# 10ethernet100.net
KiCad netlist of a schematic drawn in Altium Designer
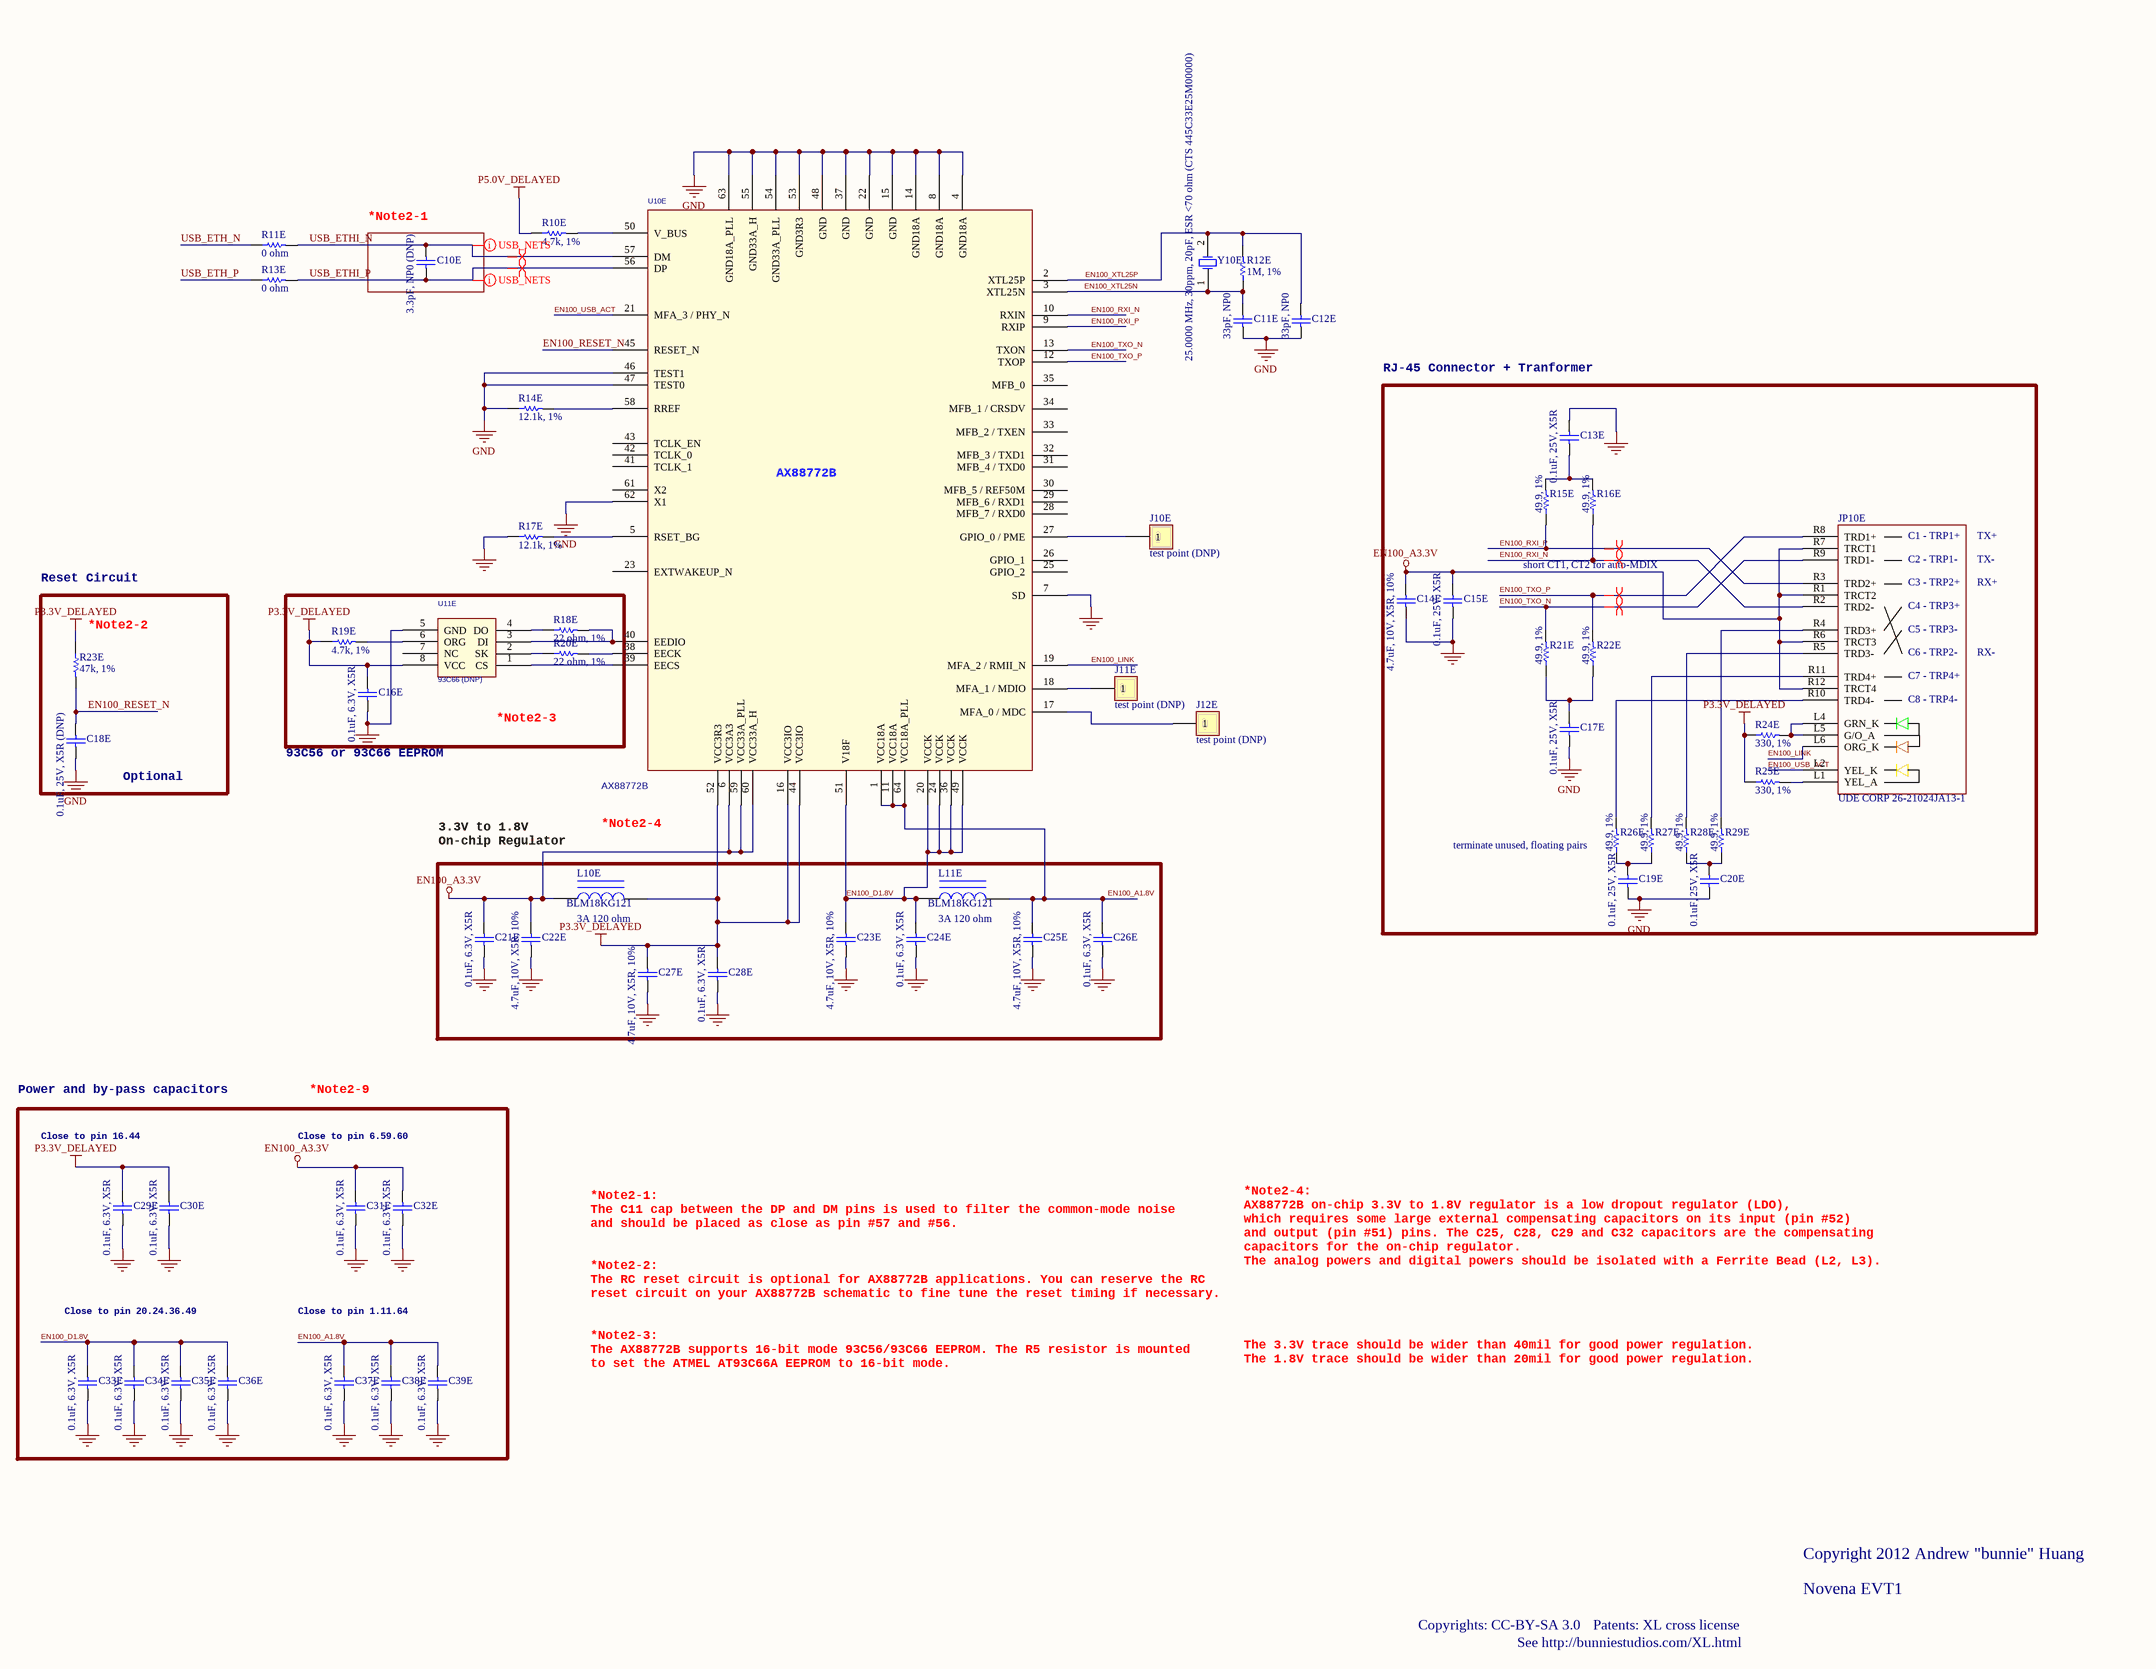
[diagram p0: 10ethernet100.SchDoc]

(export (version "E")
  (design (tool "Eeschema 10.0.6"))
  (components
    (comp (ref "C10E")
      (value "3.3pF, NP0 (DNP)")
      (footprint "CAPC1005N")
      (description "Capacitor (Semiconductor SIM Model)")
      (fields (field (name "PUBLISHER") "Altium Limited"))
      (libsource (lib "Miscellaneous Devices") (part "Cap Semi"))
    )
    (comp (ref "C11E")
      (value "33pF, NP0")
      (footprint "CAPC1005N")
      (description "Capacitor (Semiconductor SIM Model)")
      (fields (field (name "PUBLISHER") "Altium Limited"))
      (libsource (lib "Miscellaneous Devices") (part "Cap Semi"))
    )
    (comp (ref "C12E")
      (value "33pF, NP0")
      (footprint "CAPC1005N")
      (description "Capacitor (Semiconductor SIM Model)")
      (fields (field (name "PUBLISHER") "Altium Limited"))
      (libsource (lib "Miscellaneous Devices") (part "Cap Semi"))
    )
    (comp (ref "C13E")
      (value "0.1uF, 25V, X5R")
      (footprint "CAPC1005N")
      (description "Capacitor (Semiconductor SIM Model)")
      (fields (field (name "PUBLISHER") "Altium Limited"))
      (libsource (lib "Miscellaneous Devices") (part "Cap Semi"))
    )
    (comp (ref "C14E")
      (value "4.7uF, 10V, X5R, 10%")
      (footprint "CAPC1608N")
      (description "Capacitor (Semiconductor SIM Model)")
      (fields (field (name "PUBLISHER") "Altium Limited"))
      (libsource (lib "Miscellaneous Devices") (part "Cap Semi"))
    )
    (comp (ref "C15E")
      (value "0.1uF, 25V, X5R")
      (footprint "CAPC1005N")
      (description "Capacitor (Semiconductor SIM Model)")
      (fields (field (name "PUBLISHER") "Altium Limited"))
      (libsource (lib "Miscellaneous Devices") (part "Cap Semi"))
    )
    (comp (ref "C16E")
      (value "0.1uF, 6.3V, X5R")
      (footprint "CAPC0603N_B")
      (description "Capacitor (Semiconductor SIM Model)")
      (fields (field (name "PUBLISHER") "Altium Limited"))
      (libsource (lib "Miscellaneous Devices") (part "Cap Semi"))
    )
    (comp (ref "C17E")
      (value "0.1uF, 25V, X5R")
      (footprint "CAPC1005N")
      (description "Capacitor (Semiconductor SIM Model)")
      (fields (field (name "PUBLISHER") "Altium Limited"))
      (libsource (lib "Miscellaneous Devices") (part "Cap Semi"))
    )
    (comp (ref "C18E")
      (value "0.1uF, 25V, X5R (DNP)")
      (footprint "CAPC1005N")
      (description "Capacitor (Semiconductor SIM Model)")
      (fields (field (name "PUBLISHER") "Altium Limited"))
      (libsource (lib "Miscellaneous Devices") (part "Cap Semi"))
    )
    (comp (ref "C19E")
      (value "0.1uF, 25V, X5R")
      (footprint "CAPC1005N")
      (description "Capacitor (Semiconductor SIM Model)")
      (fields (field (name "PUBLISHER") "Altium Limited"))
      (libsource (lib "Miscellaneous Devices") (part "Cap Semi"))
    )
    (comp (ref "C20E")
      (value "0.1uF, 25V, X5R")
      (footprint "CAPC1005N")
      (description "Capacitor (Semiconductor SIM Model)")
      (fields (field (name "PUBLISHER") "Altium Limited"))
      (libsource (lib "Miscellaneous Devices") (part "Cap Semi"))
    )
    (comp (ref "C21E")
      (value "0.1uF, 6.3V, X5R")
      (footprint "CAPC0603N_B")
      (description "Capacitor (Semiconductor SIM Model)")
      (fields (field (name "PUBLISHER") "Altium Limited"))
      (libsource (lib "Miscellaneous Devices") (part "Cap Semi"))
    )
    (comp (ref "C22E")
      (value "4.7uF, 10V, X5R, 10%")
      (footprint "CAPC1608N")
      (description "Capacitor (Semiconductor SIM Model)")
      (fields (field (name "PUBLISHER") "Altium Limited"))
      (libsource (lib "Miscellaneous Devices") (part "Cap Semi"))
    )
    (comp (ref "C23E")
      (value "4.7uF, 10V, X5R, 10%")
      (footprint "CAPC1608N")
      (description "Capacitor (Semiconductor SIM Model)")
      (fields (field (name "PUBLISHER") "Altium Limited"))
      (libsource (lib "Miscellaneous Devices") (part "Cap Semi"))
    )
    (comp (ref "C24E")
      (value "0.1uF, 6.3V, X5R")
      (footprint "CAPC0603N_B")
      (description "Capacitor (Semiconductor SIM Model)")
      (fields (field (name "PUBLISHER") "Altium Limited"))
      (libsource (lib "Miscellaneous Devices") (part "Cap Semi"))
    )
    (comp (ref "C25E")
      (value "4.7uF, 10V, X5R, 10%")
      (footprint "CAPC1608N")
      (description "Capacitor (Semiconductor SIM Model)")
      (fields (field (name "PUBLISHER") "Altium Limited"))
      (libsource (lib "Miscellaneous Devices") (part "Cap Semi"))
    )
    (comp (ref "C26E")
      (value "0.1uF, 6.3V, X5R")
      (footprint "CAPC0603N_B")
      (description "Capacitor (Semiconductor SIM Model)")
      (fields (field (name "PUBLISHER") "Altium Limited"))
      (libsource (lib "Miscellaneous Devices") (part "Cap Semi"))
    )
    (comp (ref "C27E")
      (value "4.7uF, 10V, X5R, 10%")
      (footprint "CAPC1608N")
      (description "Capacitor (Semiconductor SIM Model)")
      (fields (field (name "PUBLISHER") "Altium Limited"))
      (libsource (lib "Miscellaneous Devices") (part "Cap Semi"))
    )
    (comp (ref "C28E")
      (value "0.1uF, 6.3V, X5R")
      (footprint "CAPC0603N_B")
      (description "Capacitor (Semiconductor SIM Model)")
      (fields (field (name "PUBLISHER") "Altium Limited"))
      (libsource (lib "Miscellaneous Devices") (part "Cap Semi"))
    )
    (comp (ref "C29E")
      (value "0.1uF, 6.3V, X5R")
      (footprint "CAPC0603N_B")
      (description "Capacitor (Semiconductor SIM Model)")
      (fields (field (name "PUBLISHER") "Altium Limited"))
      (libsource (lib "Miscellaneous Devices") (part "Cap Semi"))
    )
    (comp (ref "C30E")
      (value "0.1uF, 6.3V, X5R")
      (footprint "CAPC0603N_B")
      (description "Capacitor (Semiconductor SIM Model)")
      (fields (field (name "PUBLISHER") "Altium Limited"))
      (libsource (lib "Miscellaneous Devices") (part "Cap Semi"))
    )
    (comp (ref "C31E")
      (value "0.1uF, 6.3V, X5R")
      (footprint "CAPC0603N_B")
      (description "Capacitor (Semiconductor SIM Model)")
      (fields (field (name "PUBLISHER") "Altium Limited"))
      (libsource (lib "Miscellaneous Devices") (part "Cap Semi"))
    )
    (comp (ref "C32E")
      (value "0.1uF, 6.3V, X5R")
      (footprint "CAPC0603N_B")
      (description "Capacitor (Semiconductor SIM Model)")
      (fields (field (name "PUBLISHER") "Altium Limited"))
      (libsource (lib "Miscellaneous Devices") (part "Cap Semi"))
    )
    (comp (ref "C33E")
      (value "0.1uF, 6.3V, X5R")
      (footprint "CAPC0603N_B")
      (description "Capacitor (Semiconductor SIM Model)")
      (fields (field (name "PUBLISHER") "Altium Limited"))
      (libsource (lib "Miscellaneous Devices") (part "Cap Semi"))
    )
    (comp (ref "C34E")
      (value "0.1uF, 6.3V, X5R")
      (footprint "CAPC0603N_B")
      (description "Capacitor (Semiconductor SIM Model)")
      (fields (field (name "PUBLISHER") "Altium Limited"))
      (libsource (lib "Miscellaneous Devices") (part "Cap Semi"))
    )
    (comp (ref "C35E")
      (value "0.1uF, 6.3V, X5R")
      (footprint "CAPC0603N_B")
      (description "Capacitor (Semiconductor SIM Model)")
      (fields (field (name "PUBLISHER") "Altium Limited"))
      (libsource (lib "Miscellaneous Devices") (part "Cap Semi"))
    )
    (comp (ref "C36E")
      (value "0.1uF, 6.3V, X5R")
      (footprint "CAPC0603N_B")
      (description "Capacitor (Semiconductor SIM Model)")
      (fields (field (name "PUBLISHER") "Altium Limited"))
      (libsource (lib "Miscellaneous Devices") (part "Cap Semi"))
    )
    (comp (ref "C37E")
      (value "0.1uF, 6.3V, X5R")
      (footprint "CAPC0603N_B")
      (description "Capacitor (Semiconductor SIM Model)")
      (fields (field (name "PUBLISHER") "Altium Limited"))
      (libsource (lib "Miscellaneous Devices") (part "Cap Semi"))
    )
    (comp (ref "C38E")
      (value "0.1uF, 6.3V, X5R")
      (footprint "CAPC0603N_B")
      (description "Capacitor (Semiconductor SIM Model)")
      (fields (field (name "PUBLISHER") "Altium Limited"))
      (libsource (lib "Miscellaneous Devices") (part "Cap Semi"))
    )
    (comp (ref "C39E")
      (value "0.1uF, 6.3V, X5R")
      (footprint "CAPC0603N_B")
      (description "Capacitor (Semiconductor SIM Model)")
      (fields (field (name "PUBLISHER") "Altium Limited"))
      (libsource (lib "Miscellaneous Devices") (part "Cap Semi"))
    )
    (comp (ref "J10E")
      (value "test point (DNP)")
      (footprint "TP_SMT_38mil")
      (description "Connector")
      (libsource (lib "*") (part "CON1"))
    )
    (comp (ref "J11E")
      (value "test point (DNP)")
      (footprint "TP_SMT_38mil")
      (description "Connector")
      (libsource (lib "*") (part "CON1"))
    )
    (comp (ref "J12E")
      (value "test point (DNP)")
      (footprint "TP_SMT_38mil")
      (description "Connector")
      (libsource (lib "*") (part "CON1"))
    )
    (comp (ref "JP10E")
      (value "UDE CORP 26-21024JA13-1")
      (footprint "UDE_CORP_26-21024JA13-1")
      (description "10/100/1000BT + magnetics, symmetric, tab up, with LEDs")
      (libsource (lib "commonsch") (part "UDE_CORP_26-21024JA13-1"))
    )
    (comp (ref "L10E")
      (value "BLM18KG121")
      (footprint "INDC1608AN")
      (description "Magnetic-Core Inductor")
      (fields (field (name "ALTIUM_VALUE") "3A 120 ohm") (field (name "PUBLISHER") "Altium Limited"))
      (libsource (lib "Miscellaneous Devices") (part "Inductor Iron"))
    )
    (comp (ref "L11E")
      (value "BLM18KG121")
      (footprint "INDC1608AN")
      (description "Magnetic-Core Inductor")
      (fields (field (name "ALTIUM_VALUE") "3A 120 ohm") (field (name "PUBLISHER") "Altium Limited"))
      (libsource (lib "Miscellaneous Devices") (part "Inductor Iron"))
    )
    (comp (ref "R10E")
      (value "4.7k, 1%")
      (footprint "RESC1005N")
      (description "Resistor")
      (fields (field (name "PUBLISHER") "Altium Limited"))
      (libsource (lib "Miscellaneous Devices") (part "Res1"))
    )
    (comp (ref "R11E")
      (value "0 ohm")
      (footprint "RESC1005N")
      (description "Resistor")
      (fields (field (name "PUBLISHER") "Altium Limited"))
      (libsource (lib "Miscellaneous Devices") (part "Res1"))
    )
    (comp (ref "R12E")
      (value "1M, 1%")
      (footprint "RESC1005N")
      (description "Resistor")
      (fields (field (name "PUBLISHER") "Altium Limited"))
      (libsource (lib "Miscellaneous Devices") (part "Res1"))
    )
    (comp (ref "R13E")
      (value "0 ohm")
      (footprint "RESC1005N")
      (description "Resistor")
      (fields (field (name "PUBLISHER") "Altium Limited"))
      (libsource (lib "Miscellaneous Devices") (part "Res1"))
    )
    (comp (ref "R14E")
      (value "12.1k, 1%")
      (footprint "RESC1005N")
      (description "Resistor")
      (fields (field (name "PUBLISHER") "Altium Limited"))
      (libsource (lib "Miscellaneous Devices") (part "Res1"))
    )
    (comp (ref "R15E")
      (value "49.9, 1%")
      (footprint "RESC1005N")
      (description "Resistor")
      (fields (field (name "PUBLISHER") "Altium Limited"))
      (libsource (lib "Miscellaneous Devices") (part "Res1"))
    )
    (comp (ref "R16E")
      (value "49.9, 1%")
      (footprint "RESC1005N")
      (description "Resistor")
      (fields (field (name "PUBLISHER") "Altium Limited"))
      (libsource (lib "Miscellaneous Devices") (part "Res1"))
    )
    (comp (ref "R17E")
      (value "12.1k, 1%")
      (footprint "RESC1005N")
      (description "Resistor")
      (fields (field (name "PUBLISHER") "Altium Limited"))
      (libsource (lib "Miscellaneous Devices") (part "Res1"))
    )
    (comp (ref "R18E")
      (value "22 ohm, 1%")
      (footprint "RESC1005N")
      (description "Resistor")
      (fields (field (name "PUBLISHER") "Altium Limited"))
      (libsource (lib "Miscellaneous Devices") (part "Res1"))
    )
    (comp (ref "R19E")
      (value "4.7k, 1%")
      (footprint "RESC1005N")
      (description "Resistor")
      (fields (field (name "PUBLISHER") "Altium Limited"))
      (libsource (lib "Miscellaneous Devices") (part "Res1"))
    )
    (comp (ref "R20E")
      (value "22 ohm, 1%")
      (footprint "RESC1005N")
      (description "Resistor")
      (fields (field (name "PUBLISHER") "Altium Limited"))
      (libsource (lib "Miscellaneous Devices") (part "Res1"))
    )
    (comp (ref "R21E")
      (value "49.9, 1%")
      (footprint "RESC1005N")
      (description "Resistor")
      (fields (field (name "PUBLISHER") "Altium Limited"))
      (libsource (lib "Miscellaneous Devices") (part "Res1"))
    )
    (comp (ref "R22E")
      (value "49.9, 1%")
      (footprint "RESC1005N")
      (description "Resistor")
      (fields (field (name "PUBLISHER") "Altium Limited"))
      (libsource (lib "Miscellaneous Devices") (part "Res1"))
    )
    (comp (ref "R23E")
      (value "47k, 1%")
      (footprint "RESC1005N")
      (description "Resistor")
      (fields (field (name "PUBLISHER") "Altium Limited"))
      (libsource (lib "Miscellaneous Devices") (part "Res1"))
    )
    (comp (ref "R24E")
      (value "330, 1%")
      (footprint "RESC1005N")
      (description "Resistor")
      (fields (field (name "PUBLISHER") "Altium Limited"))
      (libsource (lib "Miscellaneous Devices") (part "Res1"))
    )
    (comp (ref "R25E")
      (value "330, 1%")
      (footprint "RESC1005N")
      (description "Resistor")
      (fields (field (name "PUBLISHER") "Altium Limited"))
      (libsource (lib "Miscellaneous Devices") (part "Res1"))
    )
    (comp (ref "R26E")
      (value "49.9, 1%")
      (footprint "RESC1005N")
      (description "Resistor")
      (fields (field (name "PUBLISHER") "Altium Limited"))
      (libsource (lib "Miscellaneous Devices") (part "Res1"))
    )
    (comp (ref "R27E")
      (value "49.9, 1%")
      (footprint "RESC1005N")
      (description "Resistor")
      (fields (field (name "PUBLISHER") "Altium Limited"))
      (libsource (lib "Miscellaneous Devices") (part "Res1"))
    )
    (comp (ref "R28E")
      (value "49.9, 1%")
      (footprint "RESC1005N")
      (description "Resistor")
      (fields (field (name "PUBLISHER") "Altium Limited"))
      (libsource (lib "Miscellaneous Devices") (part "Res1"))
    )
    (comp (ref "R29E")
      (value "49.9, 1%")
      (footprint "RESC1005N")
      (description "Resistor")
      (fields (field (name "PUBLISHER") "Altium Limited"))
      (libsource (lib "Miscellaneous Devices") (part "Res1"))
    )
    (comp (ref "U10E") (value "AX88772B") (libsource (lib "*") (part "AX88772B_28")))
    (comp (ref "U11E") (value "93C66 (DNP)") (libsource (lib "*") (part "93c66_0")))
    (comp (ref "Y10E")
      (value "25.0000 MHz, 30ppm, 20pF, ESR <70 ohm (CTS 445C33E25M00000)")
      (footprint "NDK_NX5032A")
      (description "Crystal Oscillator")
      (fields (field (name "PUBLISHER") "Altium Limited"))
      (libsource (lib "Miscellaneous Devices") (part "XTAL"))
    )
  )
  (nets
    (net (code "1") (name "/EN100_A1.8V") (class "Default")
      (node (ref "C25E") (pin "1") (pinfunction "1_1") (pintype "passive"))
      (node (ref "C26E") (pin "1") (pinfunction "1_1") (pintype "passive"))
      (node (ref "C37E") (pin "1") (pinfunction "1_1") (pintype "passive"))
      (node (ref "C38E") (pin "1") (pinfunction "1_1") (pintype "passive"))
      (node (ref "C39E") (pin "1") (pinfunction "1_1") (pintype "passive"))
      (node (ref "L11E") (pin "2") (pinfunction "2_2") (pintype "passive"))
      (node (ref "U10E") (pin "1") (pinfunction "VCC18A_1") (pintype "passive"))
      (node (ref "U10E") (pin "11") (pinfunction "VCC18A_11") (pintype "passive"))
      (node (ref "U10E") (pin "64") (pinfunction "VCC18A_PLL_64") (pintype "passive"))
    )
    (net (code "2") (name "/EN100_D1.8V") (class "Default")
      (node (ref "C23E") (pin "1") (pinfunction "1_1") (pintype "passive"))
      (node (ref "C24E") (pin "1") (pinfunction "1_1") (pintype "passive"))
      (node (ref "C33E") (pin "1") (pinfunction "1_1") (pintype "passive"))
      (node (ref "C34E") (pin "1") (pinfunction "1_1") (pintype "passive"))
      (node (ref "C35E") (pin "1") (pinfunction "1_1") (pintype "passive"))
      (node (ref "C36E") (pin "1") (pinfunction "1_1") (pintype "passive"))
      (node (ref "L11E") (pin "1") (pinfunction "1_1") (pintype "passive"))
      (node (ref "U10E") (pin "20") (pinfunction "VCCK_20") (pintype "passive"))
      (node (ref "U10E") (pin "24") (pinfunction "VCCK_24") (pintype "passive"))
      (node (ref "U10E") (pin "36") (pinfunction "VCCK_36") (pintype "passive"))
      (node (ref "U10E") (pin "49") (pinfunction "VCCK_49") (pintype "passive"))
      (node (ref "U10E") (pin "51") (pinfunction "V18F_51") (pintype "passive"))
    )
    (net (code "3") (name "/EN100_LINK") (class "Default")
      (node (ref "JP10E") (pin "L6") (pinfunction "ORG_K_L6") (pintype "passive"))
      (node (ref "U10E") (pin "19") (pinfunction "MFA_2_/_RMII_N_19") (pintype "passive"))
    )
    (net (code "4") (name "/EN100_RESET_N") (class "Default")
      (node (ref "C18E") (pin "1") (pinfunction "1_1") (pintype "passive"))
      (node (ref "R23E") (pin "2") (pinfunction "2_2") (pintype "passive"))
      (node (ref "U10E") (pin "45") (pinfunction "RESET_N_45") (pintype "passive"))
    )
    (net (code "5") (name "/EN100_RXI_N") (class "Default")
      (node (ref "JP10E") (pin "R2") (pinfunction "TRD2-_R2") (pintype "passive"))
      (node (ref "R16E") (pin "1") (pinfunction "1_1") (pintype "passive"))
      (node (ref "U10E") (pin "10") (pinfunction "RXIN_10") (pintype "passive"))
    )
    (net (code "6") (name "/EN100_RXI_P") (class "Default")
      (node (ref "JP10E") (pin "R3") (pinfunction "TRD2+_R3") (pintype "passive"))
      (node (ref "R15E") (pin "1") (pinfunction "1_1") (pintype "passive"))
      (node (ref "U10E") (pin "9") (pinfunction "RXIP_9") (pintype "passive"))
    )
    (net (code "7") (name "/EN100_TXO_N") (class "Default")
      (node (ref "JP10E") (pin "R9") (pinfunction "TRD1-_R9") (pintype "passive"))
      (node (ref "R21E") (pin "2") (pinfunction "2_2") (pintype "passive"))
      (node (ref "U10E") (pin "13") (pinfunction "TXON_13") (pintype "passive"))
    )
    (net (code "8") (name "/EN100_TXO_P") (class "Default")
      (node (ref "JP10E") (pin "R8") (pinfunction "TRD1+_R8") (pintype "passive"))
      (node (ref "R22E") (pin "2") (pinfunction "2_2") (pintype "passive"))
      (node (ref "U10E") (pin "12") (pinfunction "TXOP_12") (pintype "passive"))
    )
    (net (code "9") (name "/EN100_USB_ACT") (class "Default")
      (node (ref "JP10E") (pin "L2") (pinfunction "YEL_K_L2") (pintype "passive"))
      (node (ref "U10E") (pin "21") (pinfunction "MFA_3_/_PHY_N_21") (pintype "passive"))
    )
    (net (code "10") (name "/EN100_XTL25N") (class "Default")
      (node (ref "C11E") (pin "1") (pinfunction "1_1") (pintype "passive"))
      (node (ref "R12E") (pin "1") (pinfunction "1_1") (pintype "passive"))
      (node (ref "U10E") (pin "3") (pinfunction "XTL25N_3") (pintype "passive"))
      (node (ref "Y10E") (pin "1") (pinfunction "OSC1_1") (pintype "passive"))
    )
    (net (code "11") (name "/EN100_XTL25P") (class "Default")
      (node (ref "C12E") (pin "1") (pinfunction "1_1") (pintype "passive"))
      (node (ref "R12E") (pin "2") (pinfunction "2_2") (pintype "passive"))
      (node (ref "U10E") (pin "2") (pinfunction "XTL25P_2") (pintype "passive"))
      (node (ref "Y10E") (pin "2") (pinfunction "OSC2_2") (pintype "passive"))
    )
    (net (code "12") (name "/USB_ETHI_N") (class "Default")
      (node (ref "C10E") (pin "1") (pinfunction "1_1") (pintype "passive"))
      (node (ref "R11E") (pin "2") (pinfunction "2_2") (pintype "passive"))
      (node (ref "U10E") (pin "57") (pinfunction "DM_57") (pintype "passive"))
    )
    (net (code "13") (name "/USB_ETHI_P") (class "Default")
      (node (ref "C10E") (pin "2") (pinfunction "2_2") (pintype "passive"))
      (node (ref "R13E") (pin "2") (pinfunction "2_2") (pintype "passive"))
      (node (ref "U10E") (pin "56") (pinfunction "DP_56") (pintype "passive"))
    )
    (net (code "14") (name "/USB_ETH_N") (class "Default")
      (node (ref "R11E") (pin "1") (pinfunction "1_1") (pintype "passive"))
    )
    (net (code "15") (name "/USB_ETH_P") (class "Default")
      (node (ref "R13E") (pin "1") (pinfunction "1_1") (pintype "passive"))
    )
    (net (code "16") (name "EN100_A3.3V") (class "Default")
      (node (ref "C14E") (pin "1") (pinfunction "1_1") (pintype "passive"))
      (node (ref "C15E") (pin "1") (pinfunction "1_1") (pintype "passive"))
      (node (ref "C21E") (pin "1") (pinfunction "1_1") (pintype "passive"))
      (node (ref "C22E") (pin "1") (pinfunction "1_1") (pintype "passive"))
      (node (ref "C31E") (pin "1") (pinfunction "1_1") (pintype "passive"))
      (node (ref "C32E") (pin "1") (pinfunction "1_1") (pintype "passive"))
      (node (ref "JP10E") (pin "R1") (pinfunction "TRCT2_R1") (pintype "passive"))
      (node (ref "JP10E") (pin "R12") (pinfunction "TRCT4_R12") (pintype "passive"))
      (node (ref "JP10E") (pin "R6") (pinfunction "TRCT3_R6") (pintype "passive"))
      (node (ref "JP10E") (pin "R7") (pinfunction "TRCT1_R7") (pintype "passive"))
      (node (ref "L10E") (pin "1") (pinfunction "1_1") (pintype "passive"))
      (node (ref "U10E") (pin "59") (pinfunction "VCC33A_PLL_59") (pintype "passive"))
      (node (ref "U10E") (pin "6") (pinfunction "VCC3A3_6") (pintype "passive"))
      (node (ref "U10E") (pin "60") (pinfunction "VCC33A_H_60") (pintype "passive"))
    )
    (net (code "17") (name "GND") (class "Default")
      (node (ref "C11E") (pin "2") (pinfunction "2_2") (pintype "passive"))
      (node (ref "C12E") (pin "2") (pinfunction "2_2") (pintype "passive"))
      (node (ref "C13E") (pin "1") (pinfunction "1_1") (pintype "passive"))
      (node (ref "C14E") (pin "2") (pinfunction "2_2") (pintype "passive"))
      (node (ref "C15E") (pin "2") (pinfunction "2_2") (pintype "passive"))
      (node (ref "C16E") (pin "2") (pinfunction "2_2") (pintype "passive"))
      (node (ref "C17E") (pin "2") (pinfunction "2_2") (pintype "passive"))
      (node (ref "C18E") (pin "2") (pinfunction "2_2") (pintype "passive"))
      (node (ref "C19E") (pin "2") (pinfunction "2_2") (pintype "passive"))
      (node (ref "C20E") (pin "2") (pinfunction "2_2") (pintype "passive"))
      (node (ref "C21E") (pin "2") (pinfunction "2_2") (pintype "passive"))
      (node (ref "C22E") (pin "2") (pinfunction "2_2") (pintype "passive"))
      (node (ref "C23E") (pin "2") (pinfunction "2_2") (pintype "passive"))
      (node (ref "C24E") (pin "2") (pinfunction "2_2") (pintype "passive"))
      (node (ref "C25E") (pin "2") (pinfunction "2_2") (pintype "passive"))
      (node (ref "C26E") (pin "2") (pinfunction "2_2") (pintype "passive"))
      (node (ref "C27E") (pin "2") (pinfunction "2_2") (pintype "passive"))
      (node (ref "C28E") (pin "2") (pinfunction "2_2") (pintype "passive"))
      (node (ref "C29E") (pin "2") (pinfunction "2_2") (pintype "passive"))
      (node (ref "C30E") (pin "2") (pinfunction "2_2") (pintype "passive"))
      (node (ref "C31E") (pin "2") (pinfunction "2_2") (pintype "passive"))
      (node (ref "C32E") (pin "2") (pinfunction "2_2") (pintype "passive"))
      (node (ref "C33E") (pin "2") (pinfunction "2_2") (pintype "passive"))
      (node (ref "C34E") (pin "2") (pinfunction "2_2") (pintype "passive"))
      (node (ref "C35E") (pin "2") (pinfunction "2_2") (pintype "passive"))
      (node (ref "C36E") (pin "2") (pinfunction "2_2") (pintype "passive"))
      (node (ref "C37E") (pin "2") (pinfunction "2_2") (pintype "passive"))
      (node (ref "C38E") (pin "2") (pinfunction "2_2") (pintype "passive"))
      (node (ref "C39E") (pin "2") (pinfunction "2_2") (pintype "passive"))
      (node (ref "R14E") (pin "1") (pinfunction "1_1") (pintype "passive"))
      (node (ref "R17E") (pin "1") (pinfunction "1_1") (pintype "passive"))
      (node (ref "U10E") (pin "14") (pinfunction "GND18A_14") (pintype "passive"))
      (node (ref "U10E") (pin "15") (pinfunction "GND_15") (pintype "passive"))
      (node (ref "U10E") (pin "22") (pinfunction "GND_22") (pintype "passive"))
      (node (ref "U10E") (pin "37") (pinfunction "GND_37") (pintype "passive"))
      (node (ref "U10E") (pin "4") (pinfunction "GND18A_4") (pintype "passive"))
      (node (ref "U10E") (pin "46") (pinfunction "TEST1_46") (pintype "passive"))
      (node (ref "U10E") (pin "47") (pinfunction "TEST0_47") (pintype "passive"))
      (node (ref "U10E") (pin "48") (pinfunction "GND_48") (pintype "passive"))
      (node (ref "U10E") (pin "53") (pinfunction "GND3R3_53") (pintype "passive"))
      (node (ref "U10E") (pin "54") (pinfunction "GND33A_PLL_54") (pintype "passive"))
      (node (ref "U10E") (pin "55") (pinfunction "GND33A_H_55") (pintype "passive"))
      (node (ref "U10E") (pin "62") (pinfunction "X1_62") (pintype "passive"))
      (node (ref "U10E") (pin "63") (pinfunction "GND18A_PLL_63") (pintype "passive"))
      (node (ref "U10E") (pin "7") (pinfunction "SD_7") (pintype "passive"))
      (node (ref "U10E") (pin "8") (pinfunction "GND18A_8") (pintype "passive"))
      (node (ref "U11E") (pin "5") (pinfunction "GND_5") (pintype "passive"))
    )
    (net (code "18") (name "Net-(C13E-Pad2)") (class "Default")
      (node (ref "C13E") (pin "2") (pinfunction "2_2") (pintype "passive"))
      (node (ref "R15E") (pin "2") (pinfunction "2_2") (pintype "passive"))
      (node (ref "R16E") (pin "2") (pinfunction "2_2") (pintype "passive"))
    )
    (net (code "19") (name "Net-(C17E-Pad1)") (class "Default")
      (node (ref "C17E") (pin "1") (pinfunction "1_1") (pintype "passive"))
      (node (ref "R21E") (pin "1") (pinfunction "1_1") (pintype "passive"))
      (node (ref "R22E") (pin "1") (pinfunction "1_1") (pintype "passive"))
    )
    (net (code "20") (name "Net-(C19E-Pad1)") (class "Default")
      (node (ref "C19E") (pin "1") (pinfunction "1_1") (pintype "passive"))
      (node (ref "R26E") (pin "1") (pinfunction "1_1") (pintype "passive"))
      (node (ref "R27E") (pin "1") (pinfunction "1_1") (pintype "passive"))
    )
    (net (code "21") (name "Net-(C20E-Pad1)") (class "Default")
      (node (ref "C20E") (pin "1") (pinfunction "1_1") (pintype "passive"))
      (node (ref "R28E") (pin "1") (pinfunction "1_1") (pintype "passive"))
      (node (ref "R29E") (pin "1") (pinfunction "1_1") (pintype "passive"))
    )
    (net (code "22") (name "Net-(JP10E-GRN_K)") (class "Default")
      (node (ref "JP10E") (pin "L4") (pinfunction "GRN_K_L4") (pintype "passive"))
      (node (ref "JP10E") (pin "L5") (pinfunction "G/O_A_L5") (pintype "passive"))
      (node (ref "R24E") (pin "2") (pinfunction "2_2") (pintype "passive"))
    )
    (net (code "23") (name "Net-(JP10E-TRD3+)") (class "Default")
      (node (ref "JP10E") (pin "R4") (pinfunction "TRD3+_R4") (pintype "passive"))
      (node (ref "R29E") (pin "2") (pinfunction "2_2") (pintype "passive"))
    )
    (net (code "24") (name "Net-(JP10E-TRD3-)") (class "Default")
      (node (ref "JP10E") (pin "R5") (pinfunction "TRD3-_R5") (pintype "passive"))
      (node (ref "R28E") (pin "2") (pinfunction "2_2") (pintype "passive"))
    )
    (net (code "25") (name "Net-(JP10E-TRD4+)") (class "Default")
      (node (ref "JP10E") (pin "R11") (pinfunction "TRD4+_R11") (pintype "passive"))
      (node (ref "R27E") (pin "2") (pinfunction "2_2") (pintype "passive"))
    )
    (net (code "26") (name "Net-(JP10E-TRD4-)") (class "Default")
      (node (ref "JP10E") (pin "R10") (pinfunction "TRD4-_R10") (pintype "passive"))
      (node (ref "R26E") (pin "2") (pinfunction "2_2") (pintype "passive"))
    )
    (net (code "27") (name "Net-(JP10E-YEL_A)") (class "Default")
      (node (ref "JP10E") (pin "L1") (pinfunction "YEL_A_L1") (pintype "passive"))
      (node (ref "R25E") (pin "2") (pinfunction "2_2") (pintype "passive"))
    )
    (net (code "28") (name "Net-(U10E-EECK)") (class "Default")
      (node (ref "R20E") (pin "2") (pinfunction "2_2") (pintype "passive"))
      (node (ref "U10E") (pin "38") (pinfunction "EECK_38") (pintype "passive"))
    )
    (net (code "29") (name "Net-(U10E-EECS)") (class "Default")
      (node (ref "U10E") (pin "39") (pinfunction "EECS_39") (pintype "passive"))
      (node (ref "U11E") (pin "1") (pinfunction "CS_1") (pintype "passive"))
    )
    (net (code "30") (name "Net-(U10E-EEDIO)") (class "Default")
      (node (ref "R18E") (pin "2") (pinfunction "2_2") (pintype "passive"))
      (node (ref "U10E") (pin "40") (pinfunction "EEDIO_40") (pintype "passive"))
      (node (ref "U11E") (pin "3") (pinfunction "DI_3") (pintype "passive"))
    )
    (net (code "31") (name "Net-(U10E-GPIO_0_{slash}_PME)") (class "Default")
      (node (ref "J10E") (pin "1") (pinfunction "1_1") (pintype "passive"))
      (node (ref "U10E") (pin "27") (pinfunction "GPIO_0_/_PME_27") (pintype "passive"))
    )
    (net (code "32") (name "Net-(U10E-MFA_0_{slash}_MDC)") (class "Default")
      (node (ref "J12E") (pin "1") (pinfunction "1_1") (pintype "passive"))
      (node (ref "U10E") (pin "17") (pinfunction "MFA_0_/_MDC_17") (pintype "passive"))
    )
    (net (code "33") (name "Net-(U10E-MFA_1_{slash}_MDIO)") (class "Default")
      (node (ref "J11E") (pin "1") (pinfunction "1_1") (pintype "passive"))
      (node (ref "U10E") (pin "18") (pinfunction "MFA_1_/_MDIO_18") (pintype "passive"))
    )
    (net (code "34") (name "Net-(U10E-RREF)") (class "Default")
      (node (ref "R14E") (pin "2") (pinfunction "2_2") (pintype "passive"))
      (node (ref "U10E") (pin "58") (pinfunction "RREF_58") (pintype "passive"))
    )
    (net (code "35") (name "Net-(U10E-RSET_BG)") (class "Default")
      (node (ref "R17E") (pin "2") (pinfunction "2_2") (pintype "passive"))
      (node (ref "U10E") (pin "5") (pinfunction "RSET_BG_5") (pintype "passive"))
    )
    (net (code "36") (name "Net-(U10E-V_BUS)") (class "Default")
      (node (ref "R10E") (pin "2") (pinfunction "2_2") (pintype "passive"))
      (node (ref "U10E") (pin "50") (pinfunction "V_BUS_50") (pintype "passive"))
    )
    (net (code "37") (name "Net-(U11E-DO)") (class "Default")
      (node (ref "R18E") (pin "1") (pinfunction "1_1") (pintype "passive"))
      (node (ref "U11E") (pin "4") (pinfunction "DO_4") (pintype "passive"))
    )
    (net (code "38") (name "Net-(U11E-ORG)") (class "Default")
      (node (ref "R19E") (pin "2") (pinfunction "2_2") (pintype "passive"))
      (node (ref "U11E") (pin "6") (pinfunction "ORG_6") (pintype "passive"))
    )
    (net (code "39") (name "Net-(U11E-SK)") (class "Default")
      (node (ref "R20E") (pin "1") (pinfunction "1_1") (pintype "passive"))
      (node (ref "U11E") (pin "2") (pinfunction "SK_2") (pintype "passive"))
    )
    (net (code "40") (name "P3.3V_DELAYED") (class "Default")
      (node (ref "C16E") (pin "1") (pinfunction "1_1") (pintype "passive"))
      (node (ref "C27E") (pin "1") (pinfunction "1_1") (pintype "passive"))
      (node (ref "C28E") (pin "1") (pinfunction "1_1") (pintype "passive"))
      (node (ref "C29E") (pin "1") (pinfunction "1_1") (pintype "passive"))
      (node (ref "C30E") (pin "1") (pinfunction "1_1") (pintype "passive"))
      (node (ref "L10E") (pin "2") (pinfunction "2_2") (pintype "passive"))
      (node (ref "R19E") (pin "1") (pinfunction "1_1") (pintype "passive"))
      (node (ref "R23E") (pin "1") (pinfunction "1_1") (pintype "passive"))
      (node (ref "R24E") (pin "1") (pinfunction "1_1") (pintype "passive"))
      (node (ref "R25E") (pin "1") (pinfunction "1_1") (pintype "passive"))
      (node (ref "U10E") (pin "16") (pinfunction "VCC3IO_16") (pintype "passive"))
      (node (ref "U10E") (pin "44") (pinfunction "VCC3IO_44") (pintype "passive"))
      (node (ref "U10E") (pin "52") (pinfunction "VCC3R3_52") (pintype "passive"))
      (node (ref "U11E") (pin "8") (pinfunction "VCC_8") (pintype "passive"))
    )
    (net (code "41") (name "P5.0V_DELAYED") (class "Default")
      (node (ref "R10E") (pin "1") (pinfunction "1_1") (pintype "passive"))
    )
    (net (code "42") (name "unconnected-(U10E-EXTWAKEUP_N-Pad23)") (class "Default")
      (node (ref "U10E") (pin "23") (pinfunction "EXTWAKEUP_N_23") (pintype "passive"))
    )
    (net (code "43") (name "unconnected-(U10E-GPIO_1-Pad26)") (class "Default")
      (node (ref "U10E") (pin "26") (pinfunction "GPIO_1_26") (pintype "passive"))
    )
    (net (code "44") (name "unconnected-(U10E-GPIO_2-Pad25)") (class "Default")
      (node (ref "U10E") (pin "25") (pinfunction "GPIO_2_25") (pintype "passive"))
    )
    (net (code "45") (name "unconnected-(U10E-MFB_0-Pad35)") (class "Default")
      (node (ref "U10E") (pin "35") (pinfunction "MFB_0_35") (pintype "passive"))
    )
    (net (code "46") (name "unconnected-(U10E-MFB_1_{slash}_CRSDV-Pad34)") (class "Default")
      (node (ref "U10E") (pin "34") (pinfunction "MFB_1_/_CRSDV_34") (pintype "passive"))
    )
    (net (code "47") (name "unconnected-(U10E-MFB_2_{slash}_TXEN-Pad33)") (class "Default")
      (node (ref "U10E") (pin "33") (pinfunction "MFB_2_/_TXEN_33") (pintype "passive"))
    )
    (net (code "48") (name "unconnected-(U10E-MFB_3_{slash}_TXD1-Pad32)") (class "Default")
      (node (ref "U10E") (pin "32") (pinfunction "MFB_3_/_TXD1_32") (pintype "passive"))
    )
    (net (code "49") (name "unconnected-(U10E-MFB_4_{slash}_TXD0-Pad31)") (class "Default")
      (node (ref "U10E") (pin "31") (pinfunction "MFB_4_/_TXD0_31") (pintype "passive"))
    )
    (net (code "50") (name "unconnected-(U10E-MFB_5_{slash}_REF50M-Pad30)") (class "Default")
      (node (ref "U10E") (pin "30") (pinfunction "MFB_5_/_REF50M_30") (pintype "passive"))
    )
    (net (code "51") (name "unconnected-(U10E-MFB_6_{slash}_RXD1-Pad29)") (class "Default")
      (node (ref "U10E") (pin "29") (pinfunction "MFB_6_/_RXD1_29") (pintype "passive"))
    )
    (net (code "52") (name "unconnected-(U10E-MFB_7_{slash}_RXD0-Pad28)") (class "Default")
      (node (ref "U10E") (pin "28") (pinfunction "MFB_7_/_RXD0_28") (pintype "passive"))
    )
    (net (code "53") (name "unconnected-(U10E-TCLK_0-Pad42)") (class "Default")
      (node (ref "U10E") (pin "42") (pinfunction "TCLK_0_42") (pintype "passive"))
    )
    (net (code "54") (name "unconnected-(U10E-TCLK_1-Pad41)") (class "Default")
      (node (ref "U10E") (pin "41") (pinfunction "TCLK_1_41") (pintype "passive"))
    )
    (net (code "55") (name "unconnected-(U10E-TCLK_EN-Pad43)") (class "Default")
      (node (ref "U10E") (pin "43") (pinfunction "TCLK_EN_43") (pintype "passive"))
    )
    (net (code "56") (name "unconnected-(U10E-X2-Pad61)") (class "Default")
      (node (ref "U10E") (pin "61") (pinfunction "X2_61") (pintype "passive"))
    )
    (net (code "57") (name "unconnected-(U11E-NC-Pad7)") (class "Default")
      (node (ref "U11E") (pin "7") (pinfunction "NC_7") (pintype "passive"))
    )
  )
)
